# cpuPower.net
KiCad netlist of a schematic drawn in Altium Designer
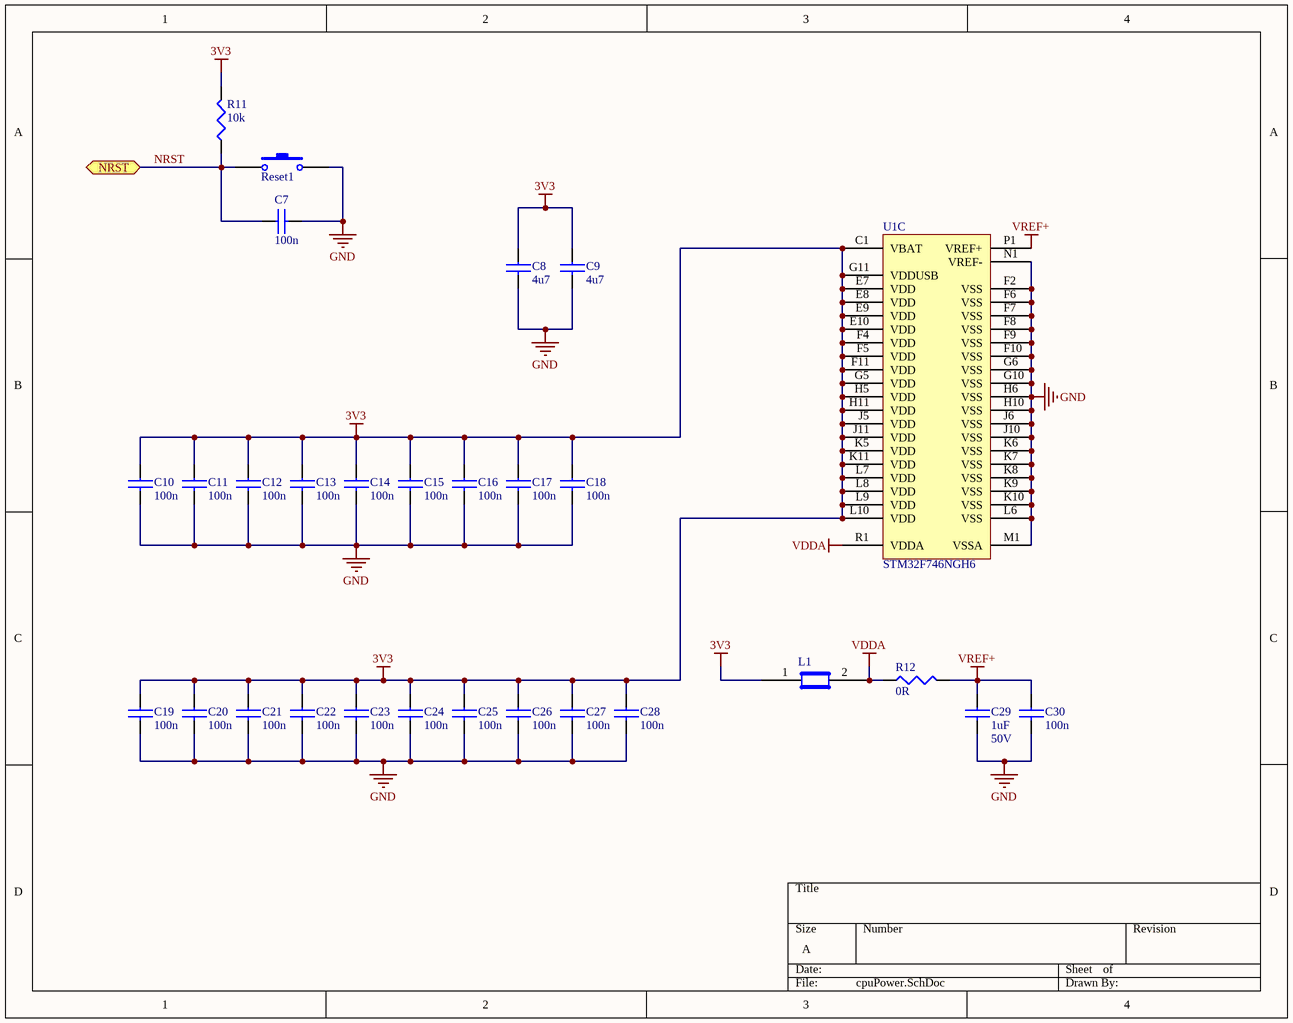
[diagram p0: cpuPower.SchDoc]

(export (version "E")
  (design (tool "Eeschema 10.0.6"))
  (components
    (comp (ref "C7")
      (value "100n")
      (footprint "C0402")
      (description "CAP CER .10UF 50V X5R 10% 0402")
      (fields
        (field (name "MANUFACTURER") "TDK Corporation")
        (field (name "MANUFACTURER PART NUMBER") "C1005X5R1H104K")
      )
      (libsource (lib "iMX6_Rex_Development_Baseboard_V1I1") (part "C1005X5R1H104K"))
    )
    (comp (ref "C8")
      (value "4u7")
      (footprint "C0402")
      (description "CAP CER 4.7UF 10V 20% X5R 0402")
      (fields
        (field (name "MANUFACTURER") "TDK Corporation")
        (field (name "MANUFACTURER PART NUMBER") "C1005X5R1A475M")
        (field (name ".CHECKED PCB") "RF")
        (field (name ".CHECKED SCH") "RF")
      )
      (libsource (lib "iMX6_Rex_Development_Baseboard_V1I1") (part "C1005X5R1A475M"))
    )
    (comp (ref "C9")
      (value "4u7")
      (footprint "C0402")
      (description "CAP CER 4.7UF 10V 20% X5R 0402")
      (fields
        (field (name "MANUFACTURER") "TDK Corporation")
        (field (name "MANUFACTURER PART NUMBER") "C1005X5R1A475M")
        (field (name ".CHECKED PCB") "RF")
        (field (name ".CHECKED SCH") "RF")
      )
      (libsource (lib "iMX6_Rex_Development_Baseboard_V1I1") (part "C1005X5R1A475M"))
    )
    (comp (ref "C10")
      (value "100n")
      (footprint "C0402")
      (description "CAP CER .10UF 50V X5R 10% 0402")
      (fields
        (field (name "MANUFACTURER") "TDK Corporation")
        (field (name "MANUFACTURER PART NUMBER") "C1005X5R1H104K")
      )
      (libsource (lib "iMX6_Rex_Development_Baseboard_V1I1") (part "C1005X5R1H104K"))
    )
    (comp (ref "C11")
      (value "100n")
      (footprint "C0402")
      (description "CAP CER .10UF 50V X5R 10% 0402")
      (fields
        (field (name "MANUFACTURER") "TDK Corporation")
        (field (name "MANUFACTURER PART NUMBER") "C1005X5R1H104K")
      )
      (libsource (lib "iMX6_Rex_Development_Baseboard_V1I1") (part "C1005X5R1H104K"))
    )
    (comp (ref "C12")
      (value "100n")
      (footprint "C0402")
      (description "CAP CER .10UF 50V X5R 10% 0402")
      (fields
        (field (name "MANUFACTURER") "TDK Corporation")
        (field (name "MANUFACTURER PART NUMBER") "C1005X5R1H104K")
      )
      (libsource (lib "iMX6_Rex_Development_Baseboard_V1I1") (part "C1005X5R1H104K"))
    )
    (comp (ref "C13")
      (value "100n")
      (footprint "C0402")
      (description "CAP CER .10UF 50V X5R 10% 0402")
      (fields
        (field (name "MANUFACTURER") "TDK Corporation")
        (field (name "MANUFACTURER PART NUMBER") "C1005X5R1H104K")
      )
      (libsource (lib "iMX6_Rex_Development_Baseboard_V1I1") (part "C1005X5R1H104K"))
    )
    (comp (ref "C14")
      (value "100n")
      (footprint "C0402")
      (description "CAP CER .10UF 50V X5R 10% 0402")
      (fields
        (field (name "MANUFACTURER") "TDK Corporation")
        (field (name "MANUFACTURER PART NUMBER") "C1005X5R1H104K")
      )
      (libsource (lib "iMX6_Rex_Development_Baseboard_V1I1") (part "C1005X5R1H104K"))
    )
    (comp (ref "C15")
      (value "100n")
      (footprint "C0402")
      (description "CAP CER .10UF 50V X5R 10% 0402")
      (fields
        (field (name "MANUFACTURER") "TDK Corporation")
        (field (name "MANUFACTURER PART NUMBER") "C1005X5R1H104K")
      )
      (libsource (lib "iMX6_Rex_Development_Baseboard_V1I1") (part "C1005X5R1H104K"))
    )
    (comp (ref "C16")
      (value "100n")
      (footprint "C0402")
      (description "CAP CER .10UF 50V X5R 10% 0402")
      (fields
        (field (name "MANUFACTURER") "TDK Corporation")
        (field (name "MANUFACTURER PART NUMBER") "C1005X5R1H104K")
      )
      (libsource (lib "iMX6_Rex_Development_Baseboard_V1I1") (part "C1005X5R1H104K"))
    )
    (comp (ref "C17")
      (value "100n")
      (footprint "C0402")
      (description "CAP CER .10UF 50V X5R 10% 0402")
      (fields
        (field (name "MANUFACTURER") "TDK Corporation")
        (field (name "MANUFACTURER PART NUMBER") "C1005X5R1H104K")
      )
      (libsource (lib "iMX6_Rex_Development_Baseboard_V1I1") (part "C1005X5R1H104K"))
    )
    (comp (ref "C18")
      (value "100n")
      (footprint "C0402")
      (description "CAP CER .10UF 50V X5R 10% 0402")
      (fields
        (field (name "MANUFACTURER") "TDK Corporation")
        (field (name "MANUFACTURER PART NUMBER") "C1005X5R1H104K")
      )
      (libsource (lib "iMX6_Rex_Development_Baseboard_V1I1") (part "C1005X5R1H104K"))
    )
    (comp (ref "C19")
      (value "100n")
      (footprint "C0402")
      (description "CAP CER .10UF 50V X5R 10% 0402")
      (fields
        (field (name "MANUFACTURER") "TDK Corporation")
        (field (name "MANUFACTURER PART NUMBER") "C1005X5R1H104K")
      )
      (libsource (lib "iMX6_Rex_Development_Baseboard_V1I1") (part "C1005X5R1H104K"))
    )
    (comp (ref "C20")
      (value "100n")
      (footprint "C0402")
      (description "CAP CER .10UF 50V X5R 10% 0402")
      (fields
        (field (name "MANUFACTURER") "TDK Corporation")
        (field (name "MANUFACTURER PART NUMBER") "C1005X5R1H104K")
      )
      (libsource (lib "iMX6_Rex_Development_Baseboard_V1I1") (part "C1005X5R1H104K"))
    )
    (comp (ref "C21")
      (value "100n")
      (footprint "C0402")
      (description "CAP CER .10UF 50V X5R 10% 0402")
      (fields
        (field (name "MANUFACTURER") "TDK Corporation")
        (field (name "MANUFACTURER PART NUMBER") "C1005X5R1H104K")
      )
      (libsource (lib "iMX6_Rex_Development_Baseboard_V1I1") (part "C1005X5R1H104K"))
    )
    (comp (ref "C22")
      (value "100n")
      (footprint "C0402")
      (description "CAP CER .10UF 50V X5R 10% 0402")
      (fields
        (field (name "MANUFACTURER") "TDK Corporation")
        (field (name "MANUFACTURER PART NUMBER") "C1005X5R1H104K")
      )
      (libsource (lib "iMX6_Rex_Development_Baseboard_V1I1") (part "C1005X5R1H104K"))
    )
    (comp (ref "C23")
      (value "100n")
      (footprint "C0402")
      (description "CAP CER .10UF 50V X5R 10% 0402")
      (fields
        (field (name "MANUFACTURER") "TDK Corporation")
        (field (name "MANUFACTURER PART NUMBER") "C1005X5R1H104K")
      )
      (libsource (lib "iMX6_Rex_Development_Baseboard_V1I1") (part "C1005X5R1H104K"))
    )
    (comp (ref "C24")
      (value "100n")
      (footprint "C0402")
      (description "CAP CER .10UF 50V X5R 10% 0402")
      (fields
        (field (name "MANUFACTURER") "TDK Corporation")
        (field (name "MANUFACTURER PART NUMBER") "C1005X5R1H104K")
      )
      (libsource (lib "iMX6_Rex_Development_Baseboard_V1I1") (part "C1005X5R1H104K"))
    )
    (comp (ref "C25")
      (value "100n")
      (footprint "C0402")
      (description "CAP CER .10UF 50V X5R 10% 0402")
      (fields
        (field (name "MANUFACTURER") "TDK Corporation")
        (field (name "MANUFACTURER PART NUMBER") "C1005X5R1H104K")
      )
      (libsource (lib "iMX6_Rex_Development_Baseboard_V1I1") (part "C1005X5R1H104K"))
    )
    (comp (ref "C26")
      (value "100n")
      (footprint "C0402")
      (description "CAP CER .10UF 50V X5R 10% 0402")
      (fields
        (field (name "MANUFACTURER") "TDK Corporation")
        (field (name "MANUFACTURER PART NUMBER") "C1005X5R1H104K")
      )
      (libsource (lib "iMX6_Rex_Development_Baseboard_V1I1") (part "C1005X5R1H104K"))
    )
    (comp (ref "C27")
      (value "100n")
      (footprint "C0402")
      (description "CAP CER .10UF 50V X5R 10% 0402")
      (fields
        (field (name "MANUFACTURER") "TDK Corporation")
        (field (name "MANUFACTURER PART NUMBER") "C1005X5R1H104K")
      )
      (libsource (lib "iMX6_Rex_Development_Baseboard_V1I1") (part "C1005X5R1H104K"))
    )
    (comp (ref "C28")
      (value "100n")
      (footprint "C0402")
      (description "CAP CER .10UF 50V X5R 10% 0402")
      (fields
        (field (name "MANUFACTURER") "TDK Corporation")
        (field (name "MANUFACTURER PART NUMBER") "C1005X5R1H104K")
      )
      (libsource (lib "iMX6_Rex_Development_Baseboard_V1I1") (part "C1005X5R1H104K"))
    )
    (comp (ref "C29")
      (value "1uF")
      (footprint "C0805")
      (description "CAP CER 1UF 50V X7R 0805")
      (fields
        (field (name "MANUFACTURER") "Murata Electronics North America")
        (field (name "MANUFACTURER PART NUMBER") "GRM21BR71H105KA12L")
        (field (name "VOLTAGE - RATED") "50V")
      )
      (libsource (lib "iMX6_Rex_Development_Baseboard_V1I1") (part "GRM21BR71H105KA12L"))
    )
    (comp (ref "C30")
      (value "100n")
      (footprint "C0402")
      (description "CAP CER .10UF 50V X5R 10% 0402")
      (fields
        (field (name "MANUFACTURER") "TDK Corporation")
        (field (name "MANUFACTURER PART NUMBER") "C1005X5R1H104K")
      )
      (libsource (lib "iMX6_Rex_Development_Baseboard_V1I1") (part "C1005X5R1H104K"))
    )
    (comp (ref "L1")
      (value "MPZ1608S601A 600OHM/1A")
      (footprint "C0603")
      (description "FERRITE CHIP BEAD 600 OHM SMD 1A")
      (fields
        (field (name "MANUFACTURER") "TDK Corporation")
        (field (name "MANUFACTURER PART NUMBER") "MPZ1608S601A")
        (field (name ".CHECKED PCB") "RF")
        (field (name ".CHECKED SCH") "RF")
      )
      (libsource (lib "iMX6_Rex_Development_Baseboard_V1I1") (part "MPZ1608S601A"))
    )
    (comp (ref "R11")
      (value "10k")
      (footprint "R0402")
      (description "RES 10.0K OHM 1/16W 1% 0402 SMD")
      (fields
        (field (name "MANUFACTURER") "Yageo")
        (field (name "MANUFACTURER PART NUMBER") "RC0402FR-0710KL")
      )
      (libsource (lib "iMX6_Rex_Development_Baseboard_V1I1") (part "RC0402FR-0710KL"))
    )
    (comp (ref "R12")
      (value "0R")
      (footprint "R0402")
      (description "RES 0.0 OHM 1/16W 0402 SMD")
      (fields
        (field (name "MANUFACTURER") "Yageo")
        (field (name "MANUFACTURER PART NUMBER") "RC0402JR-070RL")
      )
      (libsource (lib "iMX6_Rex_Development_Baseboard_V1I1") (part "RC0402JR-070RL"))
    )
    (comp (ref "Reset1")
      (value "Switch push")
      (footprint "Button Push smd")
      (description "single swithc")
      (libsource (lib "L1") (part "switch"))
    )
    (comp (ref "U1")
      (value "STM32F746NGH6")
      (footprint "STM-TFBGA216")
      (fields (field (name "PARTNUMBER") "STM32F746NG"))
      (libsource (lib "stm32f746ng") (part "STM32F746NGH6"))
    )
  )
  (nets
    (net (code "1") (name "/NRST") (class "Default")
      (node (ref "C7") (pin "1") (pinfunction "1_1") (pintype "passive"))
      (node (ref "R11") (pin "1") (pinfunction "1_1") (pintype "passive"))
      (node (ref "Reset1") (pin "1") (pinfunction "1_1") (pintype "passive"))
    )
    (net (code "2") (name "3V3") (class "Default")
      (node (ref "C10") (pin "1") (pinfunction "1_1") (pintype "passive"))
      (node (ref "C11") (pin "1") (pinfunction "1_1") (pintype "passive"))
      (node (ref "C12") (pin "1") (pinfunction "1_1") (pintype "passive"))
      (node (ref "C13") (pin "1") (pinfunction "1_1") (pintype "passive"))
      (node (ref "C14") (pin "1") (pinfunction "1_1") (pintype "passive"))
      (node (ref "C15") (pin "1") (pinfunction "1_1") (pintype "passive"))
      (node (ref "C16") (pin "1") (pinfunction "1_1") (pintype "passive"))
      (node (ref "C17") (pin "1") (pinfunction "1_1") (pintype "passive"))
      (node (ref "C18") (pin "1") (pinfunction "1_1") (pintype "passive"))
      (node (ref "C19") (pin "1") (pinfunction "1_1") (pintype "passive"))
      (node (ref "C20") (pin "1") (pinfunction "1_1") (pintype "passive"))
      (node (ref "C21") (pin "1") (pinfunction "1_1") (pintype "passive"))
      (node (ref "C22") (pin "1") (pinfunction "1_1") (pintype "passive"))
      (node (ref "C23") (pin "1") (pinfunction "1_1") (pintype "passive"))
      (node (ref "C24") (pin "1") (pinfunction "1_1") (pintype "passive"))
      (node (ref "C25") (pin "1") (pinfunction "1_1") (pintype "passive"))
      (node (ref "C26") (pin "1") (pinfunction "1_1") (pintype "passive"))
      (node (ref "C27") (pin "1") (pinfunction "1_1") (pintype "passive"))
      (node (ref "C28") (pin "1") (pinfunction "1_1") (pintype "passive"))
      (node (ref "C8") (pin "1") (pinfunction "1_1") (pintype "passive"))
      (node (ref "C9") (pin "1") (pinfunction "1_1") (pintype "passive"))
      (node (ref "L1") (pin "1") (pinfunction "1_1") (pintype "passive"))
      (node (ref "R11") (pin "2") (pinfunction "2_2") (pintype "passive"))
      (node (ref "U1") (pin "C1") (pinfunction "VBAT_C1") (pintype "power_in"))
      (node (ref "U1") (pin "E10") (pinfunction "VDD_E10") (pintype "power_in"))
      (node (ref "U1") (pin "E7") (pinfunction "VDD_E7") (pintype "power_in"))
      (node (ref "U1") (pin "E8") (pinfunction "VDD_E8") (pintype "power_in"))
      (node (ref "U1") (pin "E9") (pinfunction "VDD_E9") (pintype "power_in"))
      (node (ref "U1") (pin "F11") (pinfunction "VDD_F11") (pintype "power_in"))
      (node (ref "U1") (pin "F4") (pinfunction "VDD_F4") (pintype "power_in"))
      (node (ref "U1") (pin "F5") (pinfunction "VDD_F5") (pintype "power_in"))
      (node (ref "U1") (pin "G11") (pinfunction "VDDUSB_G11") (pintype "power_in"))
      (node (ref "U1") (pin "G5") (pinfunction "VDD_G5") (pintype "power_in"))
      (node (ref "U1") (pin "H11") (pinfunction "VDD_H11") (pintype "power_in"))
      (node (ref "U1") (pin "H5") (pinfunction "VDD_H5") (pintype "power_in"))
      (node (ref "U1") (pin "J11") (pinfunction "VDD_J11") (pintype "power_in"))
      (node (ref "U1") (pin "J5") (pinfunction "VDD_J5") (pintype "power_in"))
      (node (ref "U1") (pin "K11") (pinfunction "VDD_K11") (pintype "power_in"))
      (node (ref "U1") (pin "K5") (pinfunction "VDD_K5") (pintype "power_in"))
      (node (ref "U1") (pin "L10") (pinfunction "VDD_L10") (pintype "power_in"))
      (node (ref "U1") (pin "L7") (pinfunction "VDD_L7") (pintype "power_in"))
      (node (ref "U1") (pin "L8") (pinfunction "VDD_L8") (pintype "power_in"))
      (node (ref "U1") (pin "L9") (pinfunction "VDD_L9") (pintype "power_in"))
    )
    (net (code "3") (name "GND") (class "Default")
      (node (ref "C10") (pin "2") (pinfunction "2_2") (pintype "passive"))
      (node (ref "C11") (pin "2") (pinfunction "2_2") (pintype "passive"))
      (node (ref "C12") (pin "2") (pinfunction "2_2") (pintype "passive"))
      (node (ref "C13") (pin "2") (pinfunction "2_2") (pintype "passive"))
      (node (ref "C14") (pin "2") (pinfunction "2_2") (pintype "passive"))
      (node (ref "C15") (pin "2") (pinfunction "2_2") (pintype "passive"))
      (node (ref "C16") (pin "2") (pinfunction "2_2") (pintype "passive"))
      (node (ref "C17") (pin "2") (pinfunction "2_2") (pintype "passive"))
      (node (ref "C18") (pin "2") (pinfunction "2_2") (pintype "passive"))
      (node (ref "C19") (pin "2") (pinfunction "2_2") (pintype "passive"))
      (node (ref "C20") (pin "2") (pinfunction "2_2") (pintype "passive"))
      (node (ref "C21") (pin "2") (pinfunction "2_2") (pintype "passive"))
      (node (ref "C22") (pin "2") (pinfunction "2_2") (pintype "passive"))
      (node (ref "C23") (pin "2") (pinfunction "2_2") (pintype "passive"))
      (node (ref "C24") (pin "2") (pinfunction "2_2") (pintype "passive"))
      (node (ref "C25") (pin "2") (pinfunction "2_2") (pintype "passive"))
      (node (ref "C26") (pin "2") (pinfunction "2_2") (pintype "passive"))
      (node (ref "C27") (pin "2") (pinfunction "2_2") (pintype "passive"))
      (node (ref "C28") (pin "2") (pinfunction "2_2") (pintype "passive"))
      (node (ref "C29") (pin "2") (pinfunction "2_2") (pintype "passive"))
      (node (ref "C30") (pin "2") (pinfunction "2_2") (pintype "passive"))
      (node (ref "C7") (pin "2") (pinfunction "2_2") (pintype "passive"))
      (node (ref "C8") (pin "2") (pinfunction "2_2") (pintype "passive"))
      (node (ref "C9") (pin "2") (pinfunction "2_2") (pintype "passive"))
      (node (ref "Reset1") (pin "2") (pinfunction "2_2") (pintype "passive"))
      (node (ref "U1") (pin "F10") (pinfunction "VSS_F10") (pintype "power_in"))
      (node (ref "U1") (pin "F2") (pinfunction "VSS_F2") (pintype "power_in"))
      (node (ref "U1") (pin "F6") (pinfunction "VSS_F6") (pintype "power_in"))
      (node (ref "U1") (pin "F7") (pinfunction "VSS_F7") (pintype "power_in"))
      (node (ref "U1") (pin "F8") (pinfunction "VSS_F8") (pintype "power_in"))
      (node (ref "U1") (pin "F9") (pinfunction "VSS_F9") (pintype "power_in"))
      (node (ref "U1") (pin "G10") (pinfunction "VSS_G10") (pintype "power_in"))
      (node (ref "U1") (pin "G6") (pinfunction "VSS_G6") (pintype "power_in"))
      (node (ref "U1") (pin "H10") (pinfunction "VSS_H10") (pintype "power_in"))
      (node (ref "U1") (pin "H6") (pinfunction "VSS_H6") (pintype "power_in"))
      (node (ref "U1") (pin "J10") (pinfunction "VSS_J10") (pintype "power_in"))
      (node (ref "U1") (pin "J6") (pinfunction "VSS_J6") (pintype "power_in"))
      (node (ref "U1") (pin "K10") (pinfunction "VSS_K10") (pintype "power_in"))
      (node (ref "U1") (pin "K6") (pinfunction "VSS_K6") (pintype "power_in"))
      (node (ref "U1") (pin "K7") (pinfunction "VSS_K7") (pintype "power_in"))
      (node (ref "U1") (pin "K8") (pinfunction "VSS_K8") (pintype "power_in"))
      (node (ref "U1") (pin "K9") (pinfunction "VSS_K9") (pintype "power_in"))
      (node (ref "U1") (pin "L6") (pinfunction "VSS_L6") (pintype "power_in"))
      (node (ref "U1") (pin "M1") (pinfunction "VSSA_M1") (pintype "power_in"))
      (node (ref "U1") (pin "N1") (pinfunction "VREF-_N1") (pintype "power_in"))
    )
    (net (code "4") (name "VDDA") (class "Default")
      (node (ref "L1") (pin "2") (pinfunction "2_2") (pintype "passive"))
      (node (ref "R12") (pin "1") (pinfunction "1_1") (pintype "passive"))
      (node (ref "U1") (pin "R1") (pinfunction "VDDA_R1") (pintype "power_in"))
    )
    (net (code "5") (name "VREF+") (class "Default")
      (node (ref "C29") (pin "1") (pinfunction "1_1") (pintype "passive"))
      (node (ref "C30") (pin "1") (pinfunction "1_1") (pintype "passive"))
      (node (ref "R12") (pin "2") (pinfunction "2_2") (pintype "passive"))
      (node (ref "U1") (pin "P1") (pinfunction "VREF+_P1") (pintype "power_in"))
    )
  )
)
